# H02.net
KiCad netlist of a schematic drawn in EAGLE
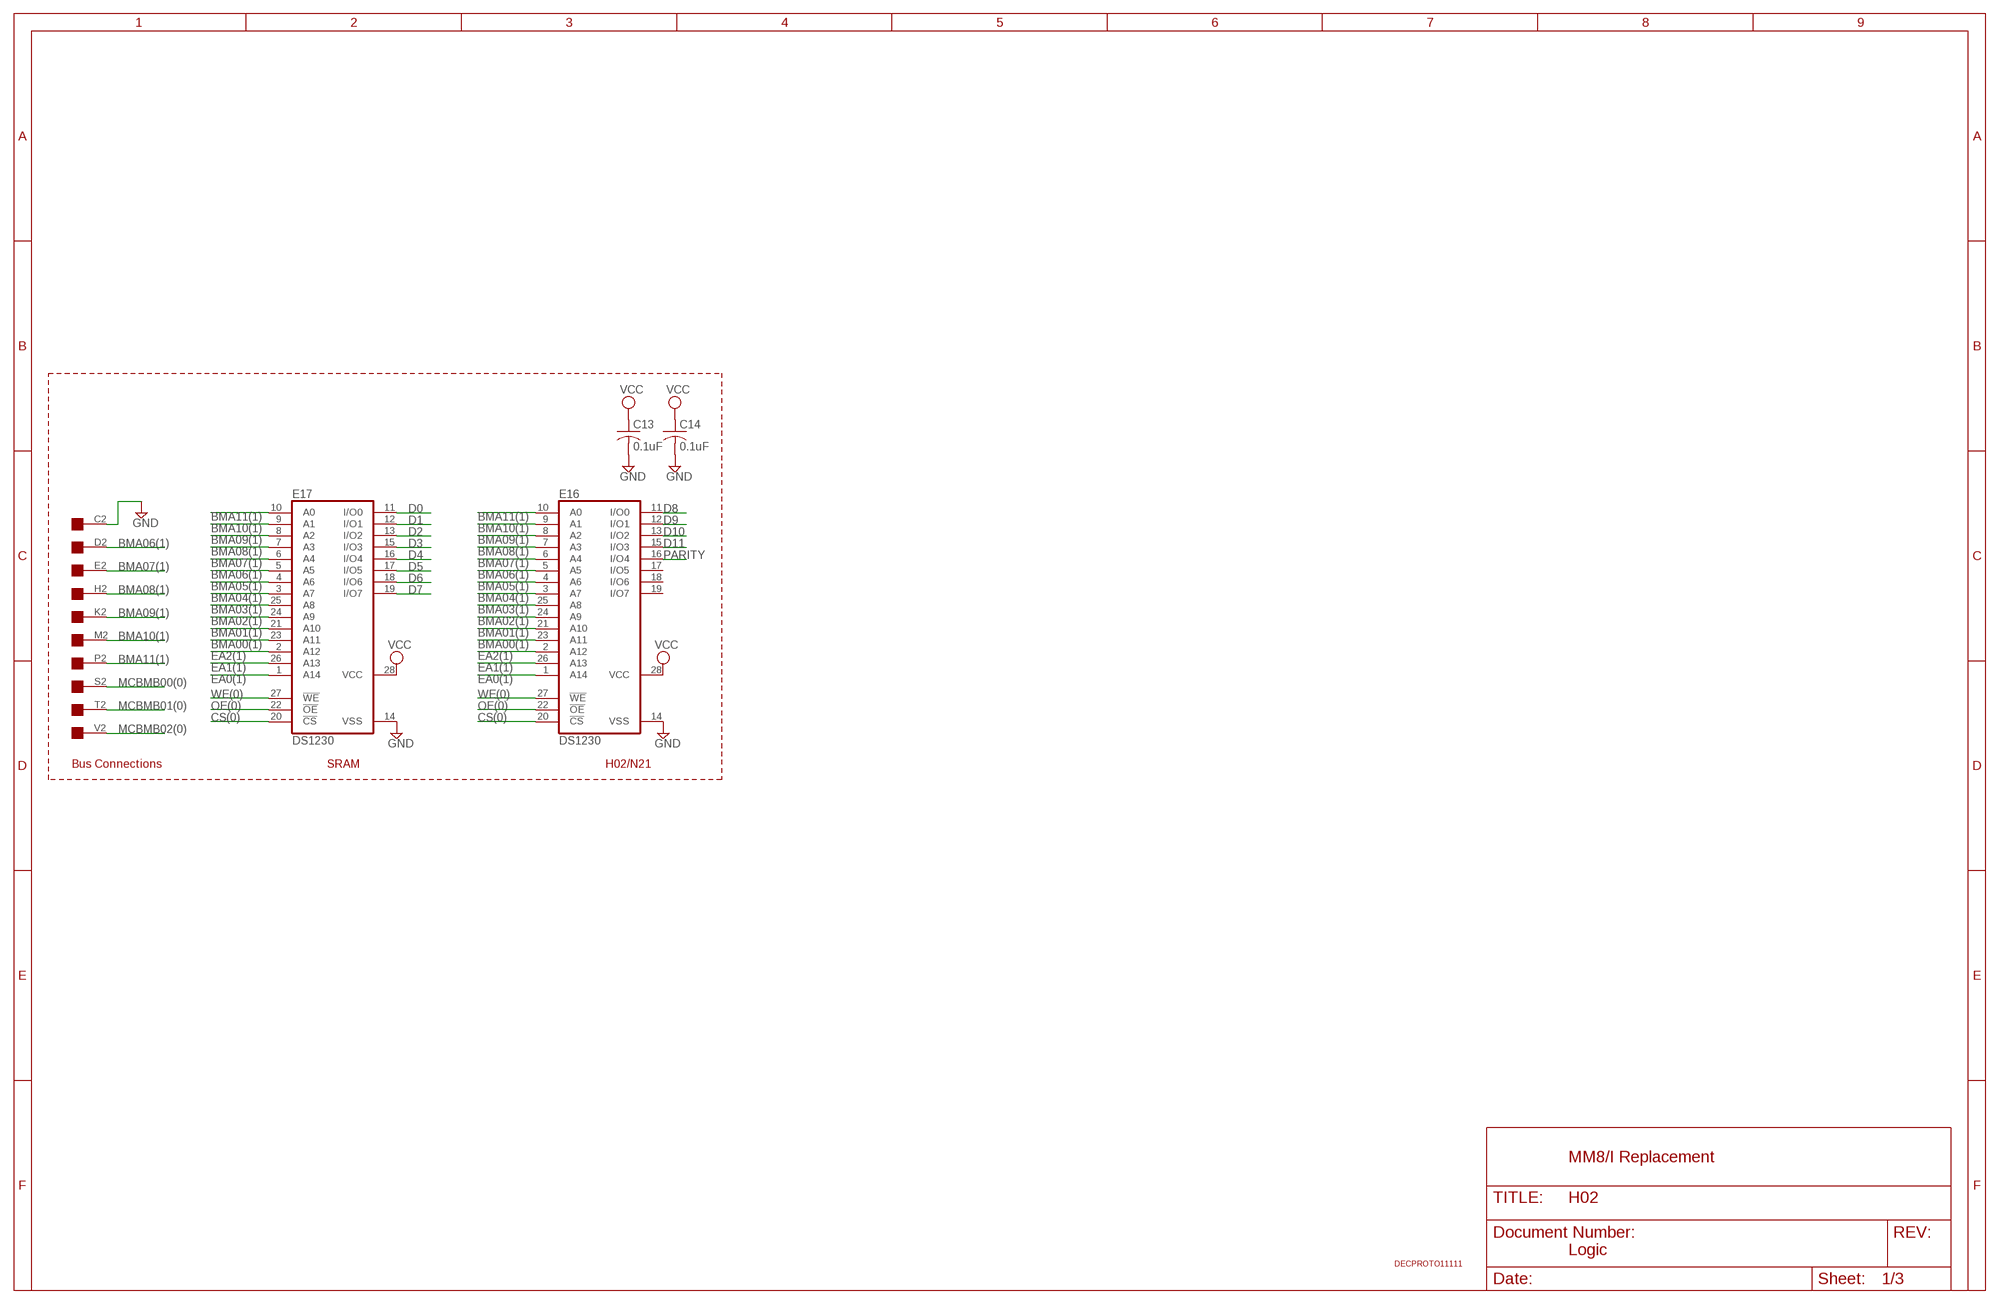
[diagram p0: schematic, sheet 1]
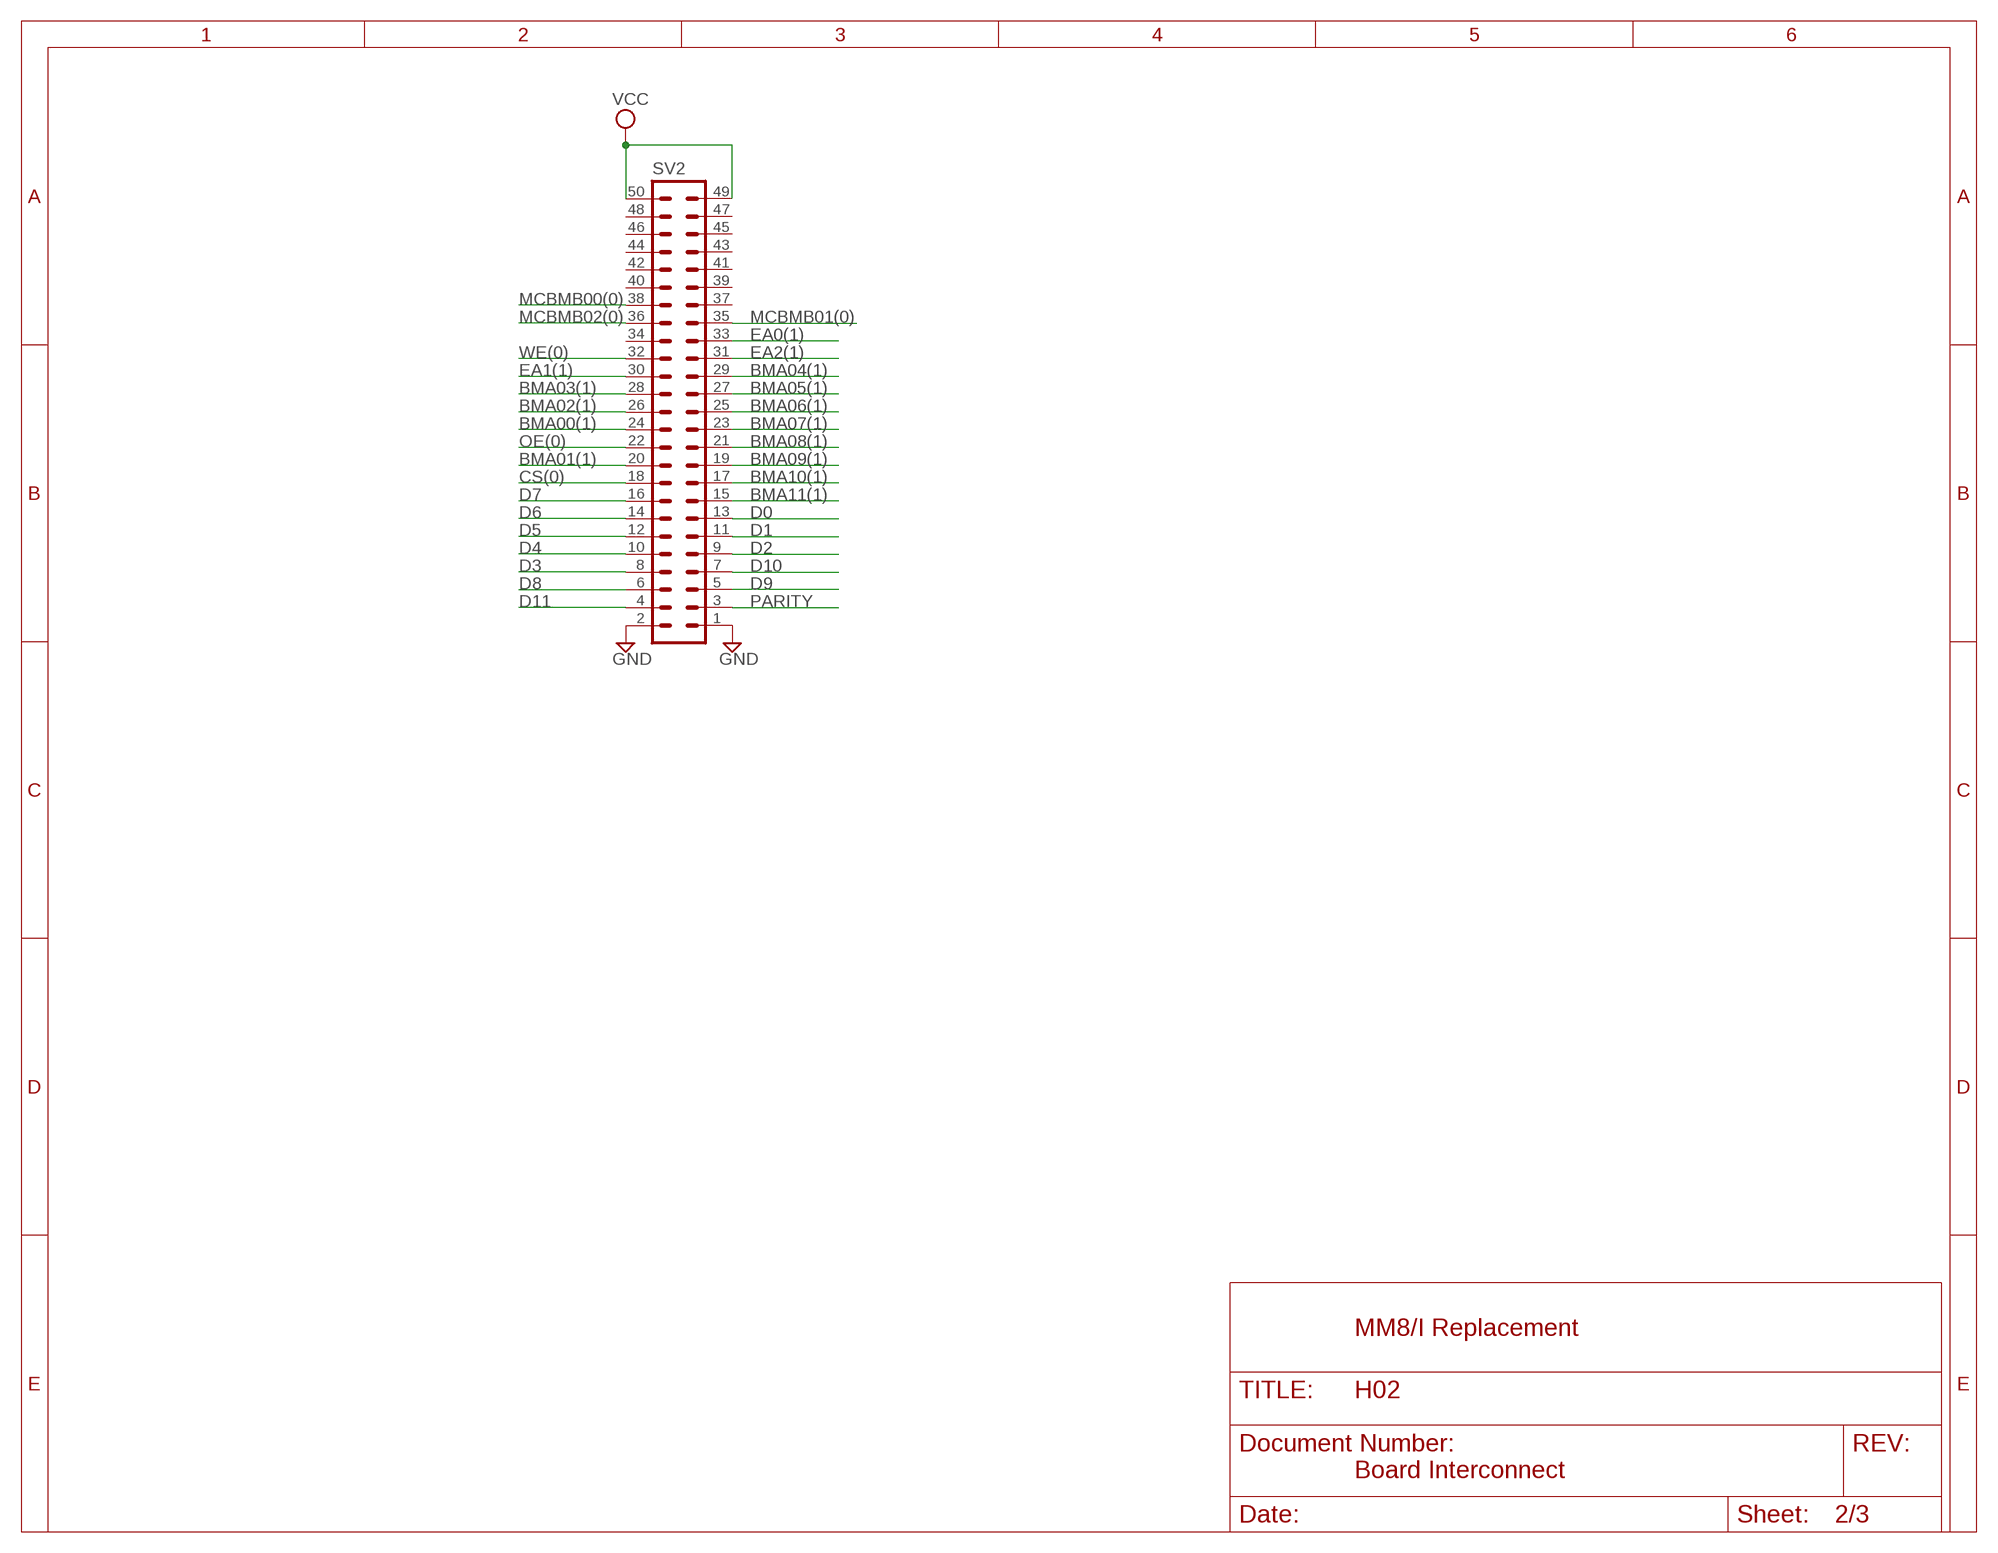
[diagram p1: schematic, sheet 2]
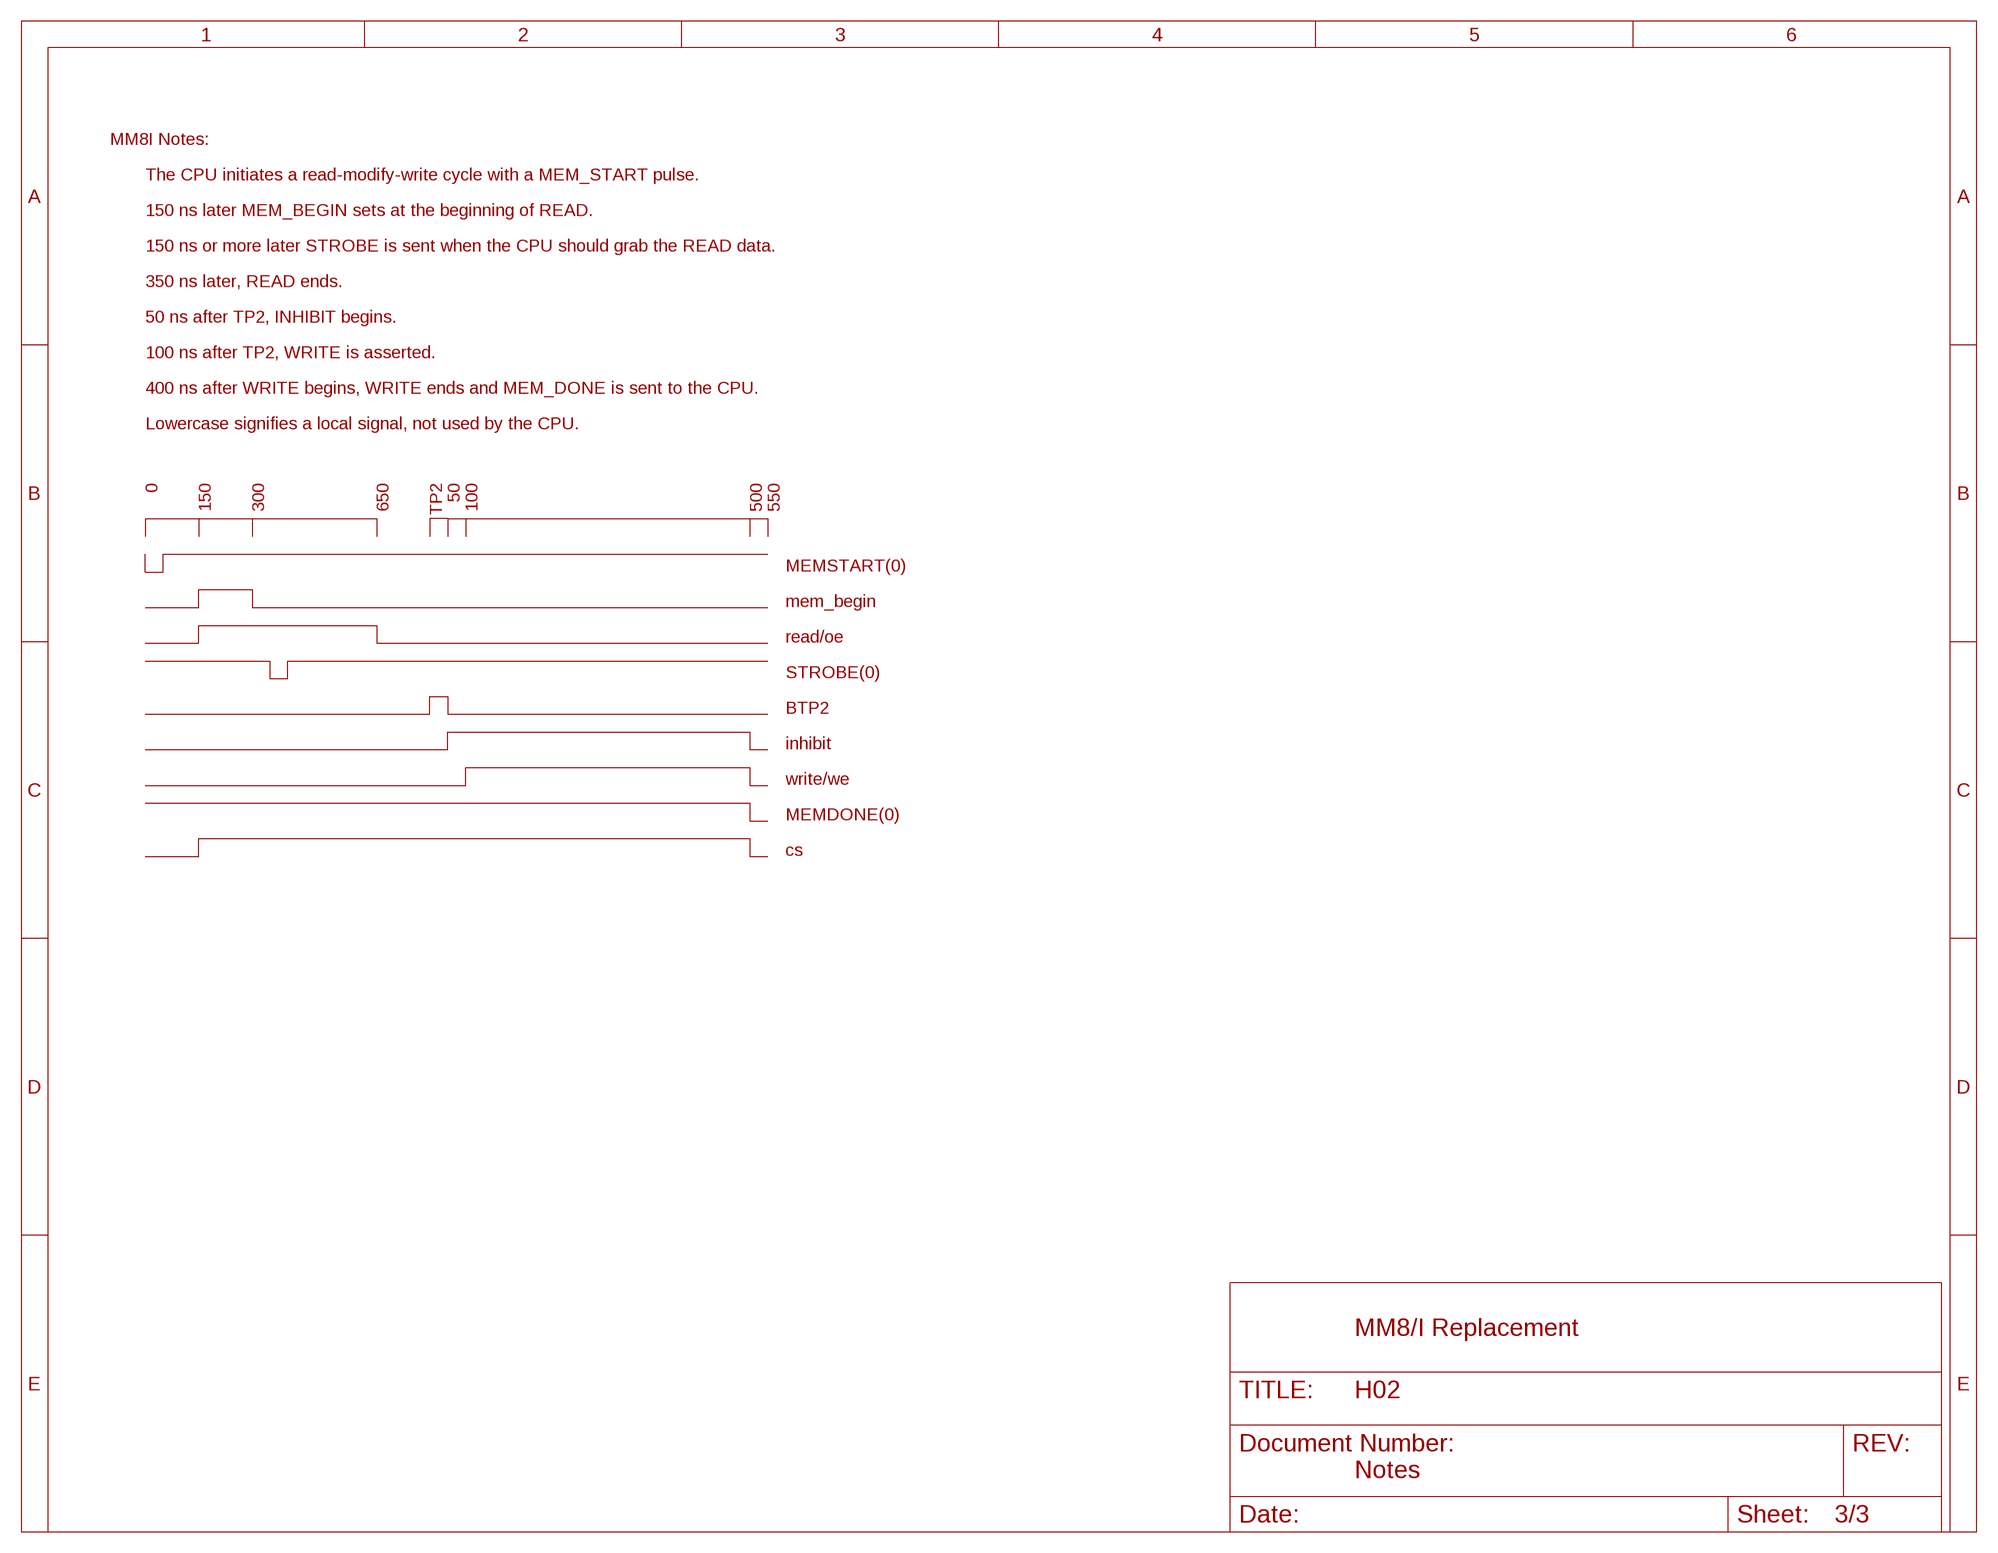
[diagram p2: schematic, sheet 3]

(export (version "E")
  (design (tool "Eeschema 10.0.6"))
  (components
    (comp (ref "C13")
      (value "0.1uF")
      (footprint "eagle-import:C050-025X075")
      (libsource (lib "eagle-import") (part "C-US050-025X075"))
    )
    (comp (ref "C14")
      (value "0.1uF")
      (footprint "eagle-import:C050-025X075")
      (libsource (lib "eagle-import") (part "C-US050-025X075"))
    )
    (comp (ref "E16")
      (value "DS1230")
      (footprint "eagle-import:DIL28-6")
      (libsource (lib "eagle-import") (part "62256P"))
    )
    (comp (ref "E17")
      (value "DS1230")
      (footprint "eagle-import:DIL28-6")
      (libsource (lib "eagle-import") (part "62256P"))
    )
    (comp (ref "H02")
      (value "EDGE-1")
      (footprint "eagle-import:EDGE-CON1")
      (libsource (lib "eagle-import") (part "EDGE-1"))
    )
    (comp (ref "U$6")
      (value "DECPROTO11111")
      (footprint "eagle-import:DECPROTO11111")
      (libsource (lib "eagle-import") (part "DECPROTO11111"))
    )
    (comp (ref "SV2")
      (value "ML50L")
      (footprint "eagle-import:ML50L")
      (libsource (lib "eagle-import") (part "ML50L"))
    )
  )
  (nets
    (net (code "1") (name "BMA00(1)") (class "Default")
      (node (ref "E16") (pin "23") (pinfunction "A11_23") (pintype "input"))
      (node (ref "E17") (pin "23") (pinfunction "A11_23") (pintype "input"))
      (node (ref "SV2") (pin "24") (pinfunction "24_24") (pintype "passive"))
    )
    (net (code "2") (name "BMA01(1)") (class "Default")
      (node (ref "E16") (pin "21") (pinfunction "A10_21") (pintype "input"))
      (node (ref "E17") (pin "21") (pinfunction "A10_21") (pintype "input"))
      (node (ref "SV2") (pin "20") (pinfunction "20_20") (pintype "passive"))
    )
    (net (code "3") (name "BMA02(1)") (class "Default")
      (node (ref "E16") (pin "24") (pinfunction "A9_24") (pintype "input"))
      (node (ref "E17") (pin "24") (pinfunction "A9_24") (pintype "input"))
      (node (ref "SV2") (pin "26") (pinfunction "26_26") (pintype "passive"))
    )
    (net (code "4") (name "BMA03(1)") (class "Default")
      (node (ref "E16") (pin "25") (pinfunction "A8_25") (pintype "input"))
      (node (ref "E17") (pin "25") (pinfunction "A8_25") (pintype "input"))
      (node (ref "SV2") (pin "28") (pinfunction "28_28") (pintype "passive"))
    )
    (net (code "5") (name "BMA04(1)") (class "Default")
      (node (ref "E16") (pin "3") (pinfunction "A7_3") (pintype "input"))
      (node (ref "E17") (pin "3") (pinfunction "A7_3") (pintype "input"))
      (node (ref "SV2") (pin "29") (pinfunction "29_29") (pintype "passive"))
    )
    (net (code "6") (name "BMA05(1)") (class "Default")
      (node (ref "E16") (pin "4") (pinfunction "A6_4") (pintype "input"))
      (node (ref "E17") (pin "4") (pinfunction "A6_4") (pintype "input"))
      (node (ref "SV2") (pin "27") (pinfunction "27_27") (pintype "passive"))
    )
    (net (code "7") (name "BMA06(1)") (class "Default")
      (node (ref "E16") (pin "5") (pinfunction "A5_5") (pintype "input"))
      (node (ref "E17") (pin "5") (pinfunction "A5_5") (pintype "input"))
      (node (ref "H02") (pin "D2") (pinfunction "1_D2") (pintype "bidirectional"))
      (node (ref "SV2") (pin "25") (pinfunction "25_25") (pintype "passive"))
    )
    (net (code "8") (name "BMA07(1)") (class "Default")
      (node (ref "E16") (pin "6") (pinfunction "A4_6") (pintype "input"))
      (node (ref "E17") (pin "6") (pinfunction "A4_6") (pintype "input"))
      (node (ref "H02") (pin "E2") (pinfunction "1_E2") (pintype "bidirectional"))
      (node (ref "SV2") (pin "23") (pinfunction "23_23") (pintype "passive"))
    )
    (net (code "9") (name "BMA08(1)") (class "Default")
      (node (ref "E16") (pin "7") (pinfunction "A3_7") (pintype "input"))
      (node (ref "E17") (pin "7") (pinfunction "A3_7") (pintype "input"))
      (node (ref "H02") (pin "H2") (pinfunction "1_H2") (pintype "bidirectional"))
      (node (ref "SV2") (pin "21") (pinfunction "21_21") (pintype "passive"))
    )
    (net (code "10") (name "BMA09(1)") (class "Default")
      (node (ref "E16") (pin "8") (pinfunction "A2_8") (pintype "input"))
      (node (ref "E17") (pin "8") (pinfunction "A2_8") (pintype "input"))
      (node (ref "H02") (pin "K2") (pinfunction "1_K2") (pintype "bidirectional"))
      (node (ref "SV2") (pin "19") (pinfunction "19_19") (pintype "passive"))
    )
    (net (code "11") (name "BMA10(1)") (class "Default")
      (node (ref "E16") (pin "9") (pinfunction "A1_9") (pintype "input"))
      (node (ref "E17") (pin "9") (pinfunction "A1_9") (pintype "input"))
      (node (ref "H02") (pin "M2") (pinfunction "1_M2") (pintype "bidirectional"))
      (node (ref "SV2") (pin "17") (pinfunction "17_17") (pintype "passive"))
    )
    (net (code "12") (name "BMA11(1)") (class "Default")
      (node (ref "E16") (pin "10") (pinfunction "A0_10") (pintype "input"))
      (node (ref "E17") (pin "10") (pinfunction "A0_10") (pintype "input"))
      (node (ref "H02") (pin "P2") (pinfunction "1_P2") (pintype "bidirectional"))
      (node (ref "SV2") (pin "15") (pinfunction "15_15") (pintype "passive"))
    )
    (net (code "13") (name "CS(0)") (class "Default")
      (node (ref "E16") (pin "20") (pinfunction "~{CS}_20") (pintype "input"))
      (node (ref "E17") (pin "20") (pinfunction "~{CS}_20") (pintype "input"))
      (node (ref "SV2") (pin "18") (pinfunction "18_18") (pintype "passive"))
    )
    (net (code "14") (name "D0") (class "Default")
      (node (ref "E17") (pin "11") (pinfunction "I/O0_11") (pintype "bidirectional"))
      (node (ref "SV2") (pin "13") (pinfunction "13_13") (pintype "passive"))
    )
    (net (code "15") (name "D1") (class "Default")
      (node (ref "E17") (pin "12") (pinfunction "I/O1_12") (pintype "bidirectional"))
      (node (ref "SV2") (pin "11") (pinfunction "11_11") (pintype "passive"))
    )
    (net (code "16") (name "D2") (class "Default")
      (node (ref "E17") (pin "13") (pinfunction "I/O2_13") (pintype "bidirectional"))
      (node (ref "SV2") (pin "9") (pinfunction "9_9") (pintype "passive"))
    )
    (net (code "17") (name "D3") (class "Default")
      (node (ref "E17") (pin "15") (pinfunction "I/O3_15") (pintype "bidirectional"))
      (node (ref "SV2") (pin "8") (pinfunction "8_8") (pintype "passive"))
    )
    (net (code "18") (name "D4") (class "Default")
      (node (ref "E17") (pin "16") (pinfunction "I/O4_16") (pintype "bidirectional"))
      (node (ref "SV2") (pin "10") (pinfunction "10_10") (pintype "passive"))
    )
    (net (code "19") (name "D5") (class "Default")
      (node (ref "E17") (pin "17") (pinfunction "I/O5_17") (pintype "bidirectional"))
      (node (ref "SV2") (pin "12") (pinfunction "12_12") (pintype "passive"))
    )
    (net (code "20") (name "D6") (class "Default")
      (node (ref "E17") (pin "18") (pinfunction "I/O6_18") (pintype "bidirectional"))
      (node (ref "SV2") (pin "14") (pinfunction "14_14") (pintype "passive"))
    )
    (net (code "21") (name "D7") (class "Default")
      (node (ref "E17") (pin "19") (pinfunction "I/O7_19") (pintype "bidirectional"))
      (node (ref "SV2") (pin "16") (pinfunction "16_16") (pintype "passive"))
    )
    (net (code "22") (name "D8") (class "Default")
      (node (ref "E16") (pin "11") (pinfunction "I/O0_11") (pintype "bidirectional"))
      (node (ref "SV2") (pin "6") (pinfunction "6_6") (pintype "passive"))
    )
    (net (code "23") (name "D9") (class "Default")
      (node (ref "E16") (pin "12") (pinfunction "I/O1_12") (pintype "bidirectional"))
      (node (ref "SV2") (pin "5") (pinfunction "5_5") (pintype "passive"))
    )
    (net (code "24") (name "D10") (class "Default")
      (node (ref "E16") (pin "13") (pinfunction "I/O2_13") (pintype "bidirectional"))
      (node (ref "SV2") (pin "7") (pinfunction "7_7") (pintype "passive"))
    )
    (net (code "25") (name "D11") (class "Default")
      (node (ref "E16") (pin "15") (pinfunction "I/O3_15") (pintype "bidirectional"))
      (node (ref "SV2") (pin "4") (pinfunction "4_4") (pintype "passive"))
    )
    (net (code "26") (name "EA0(1)") (class "Default")
      (node (ref "E16") (pin "1") (pinfunction "A14_1") (pintype "input"))
      (node (ref "E17") (pin "1") (pinfunction "A14_1") (pintype "input"))
      (node (ref "SV2") (pin "33") (pinfunction "33_33") (pintype "passive"))
    )
    (net (code "27") (name "EA1(1)") (class "Default")
      (node (ref "E16") (pin "26") (pinfunction "A13_26") (pintype "input"))
      (node (ref "E17") (pin "26") (pinfunction "A13_26") (pintype "input"))
      (node (ref "SV2") (pin "30") (pinfunction "30_30") (pintype "passive"))
    )
    (net (code "28") (name "EA2(1)") (class "Default")
      (node (ref "E16") (pin "2") (pinfunction "A12_2") (pintype "input"))
      (node (ref "E17") (pin "2") (pinfunction "A12_2") (pintype "input"))
      (node (ref "SV2") (pin "31") (pinfunction "31_31") (pintype "passive"))
    )
    (net (code "29") (name "GND") (class "Default")
      (node (ref "C13") (pin "2") (pinfunction "2_2") (pintype "passive"))
      (node (ref "C14") (pin "2") (pinfunction "2_2") (pintype "passive"))
      (node (ref "E16") (pin "14") (pinfunction "VSS_14") (pintype "power_in"))
      (node (ref "E17") (pin "14") (pinfunction "VSS_14") (pintype "power_in"))
      (node (ref "H02") (pin "C2") (pinfunction "1_C2") (pintype "bidirectional"))
      (node (ref "SV2") (pin "1") (pinfunction "1_1") (pintype "passive"))
      (node (ref "SV2") (pin "2") (pinfunction "2_2") (pintype "passive"))
    )
    (net (code "30") (name "MCBMB00(0)") (class "Default")
      (node (ref "H02") (pin "S2") (pinfunction "1_S2") (pintype "bidirectional"))
      (node (ref "SV2") (pin "38") (pinfunction "38_38") (pintype "passive"))
    )
    (net (code "31") (name "MCBMB01(0)") (class "Default")
      (node (ref "H02") (pin "T2") (pinfunction "1_T2") (pintype "bidirectional"))
      (node (ref "SV2") (pin "35") (pinfunction "35_35") (pintype "passive"))
    )
    (net (code "32") (name "MCBMB02(0)") (class "Default")
      (node (ref "H02") (pin "V2") (pinfunction "1_V2") (pintype "bidirectional"))
      (node (ref "SV2") (pin "36") (pinfunction "36_36") (pintype "passive"))
    )
    (net (code "33") (name "OE(0)") (class "Default")
      (node (ref "E16") (pin "22") (pinfunction "~{OE}_22") (pintype "input"))
      (node (ref "E17") (pin "22") (pinfunction "~{OE}_22") (pintype "input"))
      (node (ref "SV2") (pin "22") (pinfunction "22_22") (pintype "passive"))
    )
    (net (code "34") (name "PARITY") (class "Default")
      (node (ref "E16") (pin "16") (pinfunction "I/O4_16") (pintype "bidirectional"))
      (node (ref "SV2") (pin "3") (pinfunction "3_3") (pintype "passive"))
    )
    (net (code "35") (name "VCC") (class "Default")
      (node (ref "C13") (pin "1") (pinfunction "1_1") (pintype "passive"))
      (node (ref "C14") (pin "1") (pinfunction "1_1") (pintype "passive"))
      (node (ref "E16") (pin "28") (pinfunction "VCC_28") (pintype "power_in"))
      (node (ref "E17") (pin "28") (pinfunction "VCC_28") (pintype "power_in"))
      (node (ref "SV2") (pin "49") (pinfunction "49_49") (pintype "passive"))
      (node (ref "SV2") (pin "50") (pinfunction "50_50") (pintype "passive"))
    )
    (net (code "36") (name "WE(0)") (class "Default")
      (node (ref "E16") (pin "27") (pinfunction "~{WE}_27") (pintype "input"))
      (node (ref "E17") (pin "27") (pinfunction "~{WE}_27") (pintype "input"))
      (node (ref "SV2") (pin "32") (pinfunction "32_32") (pintype "passive"))
    )
    (net (code "37") (name "unconnected-(E16-I{slash}O5-Pad17)") (class "Default")
      (node (ref "E16") (pin "17") (pinfunction "I/O5_17") (pintype "bidirectional"))
    )
    (net (code "38") (name "unconnected-(E16-I{slash}O6-Pad18)") (class "Default")
      (node (ref "E16") (pin "18") (pinfunction "I/O6_18") (pintype "bidirectional"))
    )
    (net (code "39") (name "unconnected-(E16-I{slash}O7-Pad19)") (class "Default")
      (node (ref "E16") (pin "19") (pinfunction "I/O7_19") (pintype "bidirectional"))
    )
    (net (code "40") (name "unconnected-(SV2-Pad34)") (class "Default")
      (node (ref "SV2") (pin "34") (pinfunction "34_34") (pintype "passive"))
    )
    (net (code "41") (name "unconnected-(SV2-Pad37)") (class "Default")
      (node (ref "SV2") (pin "37") (pinfunction "37_37") (pintype "passive"))
    )
    (net (code "42") (name "unconnected-(SV2-Pad39)") (class "Default")
      (node (ref "SV2") (pin "39") (pinfunction "39_39") (pintype "passive"))
    )
    (net (code "43") (name "unconnected-(SV2-Pad40)") (class "Default")
      (node (ref "SV2") (pin "40") (pinfunction "40_40") (pintype "passive"))
    )
    (net (code "44") (name "unconnected-(SV2-Pad41)") (class "Default")
      (node (ref "SV2") (pin "41") (pinfunction "41_41") (pintype "passive"))
    )
    (net (code "45") (name "unconnected-(SV2-Pad42)") (class "Default")
      (node (ref "SV2") (pin "42") (pinfunction "42_42") (pintype "passive"))
    )
    (net (code "46") (name "unconnected-(SV2-Pad43)") (class "Default")
      (node (ref "SV2") (pin "43") (pinfunction "43_43") (pintype "passive"))
    )
    (net (code "47") (name "unconnected-(SV2-Pad44)") (class "Default")
      (node (ref "SV2") (pin "44") (pinfunction "44_44") (pintype "passive"))
    )
    (net (code "48") (name "unconnected-(SV2-Pad45)") (class "Default")
      (node (ref "SV2") (pin "45") (pinfunction "45_45") (pintype "passive"))
    )
    (net (code "49") (name "unconnected-(SV2-Pad46)") (class "Default")
      (node (ref "SV2") (pin "46") (pinfunction "46_46") (pintype "passive"))
    )
    (net (code "50") (name "unconnected-(SV2-Pad47)") (class "Default")
      (node (ref "SV2") (pin "47") (pinfunction "47_47") (pintype "passive"))
    )
    (net (code "51") (name "unconnected-(SV2-Pad48)") (class "Default")
      (node (ref "SV2") (pin "48") (pinfunction "48_48") (pintype "passive"))
    )
  )
)
